# IC3.net
KiCad netlist of a schematic drawn in Altium Designer
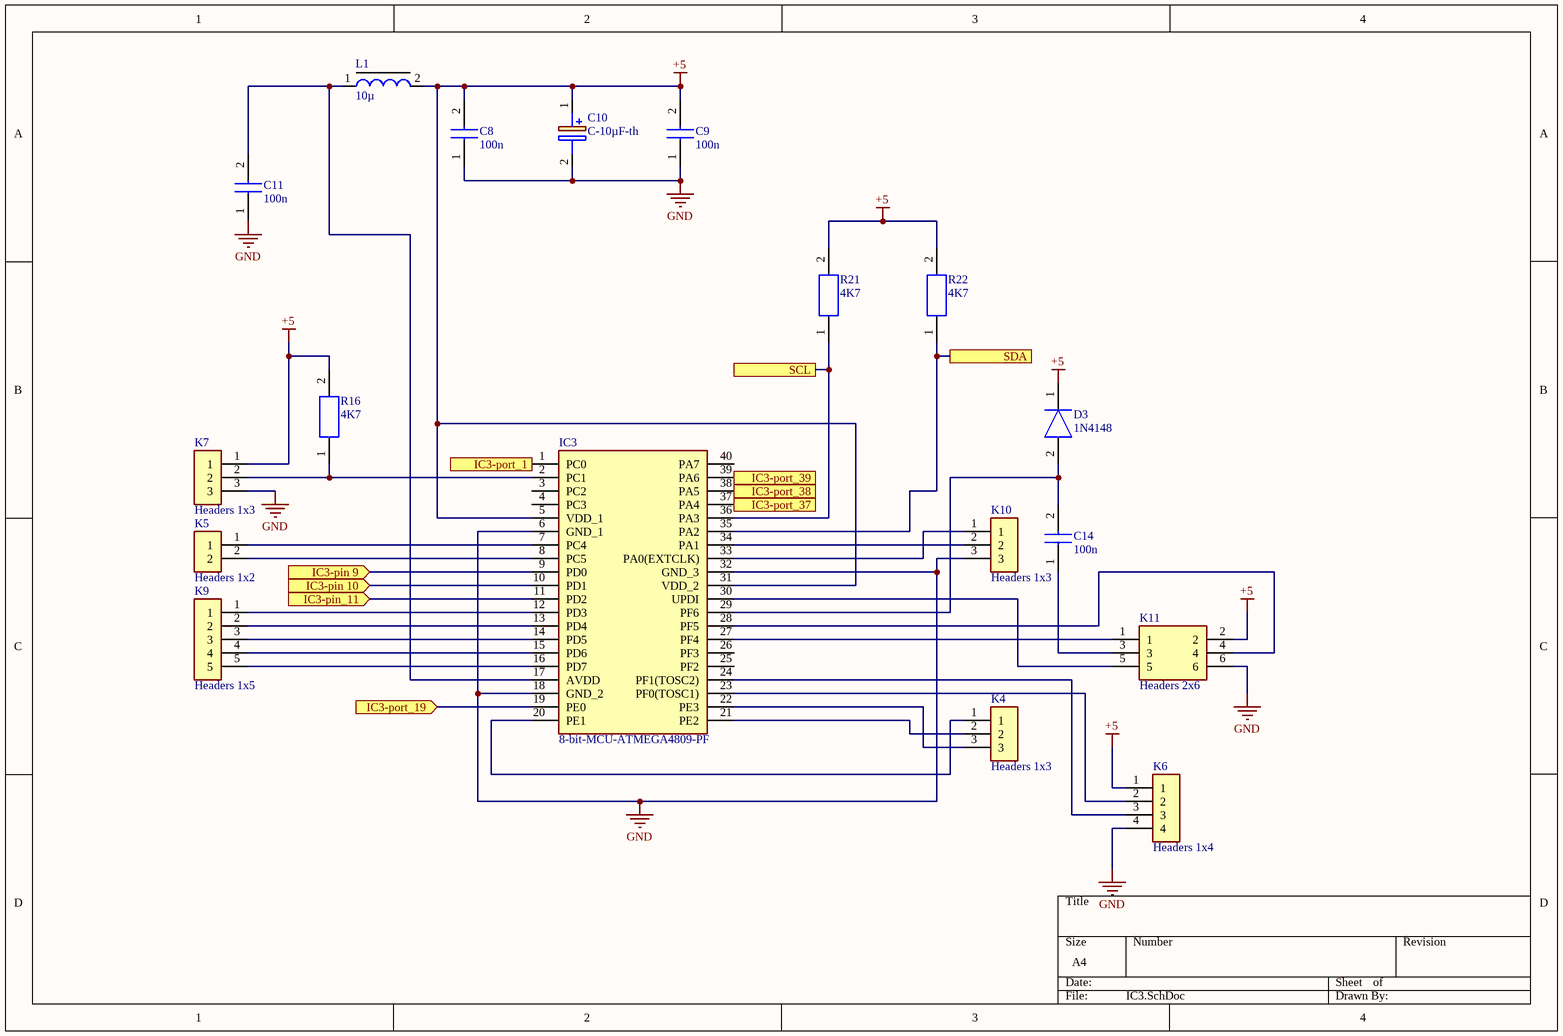
[diagram p0: IC3.SchDoc]

(export (version "E")
  (design (tool "Eeschema 10.0.6"))
  (components
    (comp (ref "C8")
      (value "100n")
      (footprint "C-0805-smd")
      (description "Capacitor")
      (fields (field (name "MANUFACTURER_PART_NUMBER") "C0805C301G5GACTU"))
      (libsource (lib "project-2022") (part "C-0805-smd"))
    )
    (comp (ref "C9")
      (value "100n")
      (footprint "C-0805-smd")
      (description "Capacitor")
      (fields (field (name "MANUFACTURER_PART_NUMBER") "C0805C301G5GACTU"))
      (libsource (lib "project-2022") (part "C-0805-smd"))
    )
    (comp (ref "C10")
      (value "C-10µF-th")
      (footprint "C-10µF-th")
      (description "Capacitor Polarised")
      (fields
        (field (name "MOUSER2 PART NUMBER") "667-ECA-1HM100I")
        (field (name "MANUFACTURER_PART_NUMBER") "ECA-1HM100I")
      )
      (libsource (lib "project-2022") (part "C-10µF-th"))
    )
    (comp (ref "C11")
      (value "100n")
      (footprint "C-0805-smd")
      (description "Capacitor")
      (fields (field (name "MANUFACTURER_PART_NUMBER") "C0805C301G5GACTU"))
      (libsource (lib "project-2022") (part "C-0805-smd"))
    )
    (comp (ref "C14")
      (value "100n")
      (footprint "C-0805-smd")
      (description "Capacitor")
      (fields (field (name "MANUFACTURER_PART_NUMBER") "C0805C301G5GACTU"))
      (libsource (lib "project-2022") (part "C-0805-smd"))
    )
    (comp (ref "D3")
      (value "1N4148")
      (footprint "1N4148")
      (description "Diode")
      (libsource (lib "project-2022") (part "1N4148"))
    )
    (comp (ref "IC3")
      (value "8-bit-MCU-ATMEGA4809-PF")
      (footprint "8-bit-MCU-ATMEGA4809-PF")
      (description "Integrated Circuit")
      (fields
        (field (name "MOUSER2 PART NUMBER") "556-ATMEGA4809-PF")
        (field (name "MANUFACTURER_PART_NUMBER") "ATMEGA4809-PF")
      )
      (libsource (lib "project-2022") (part "8-bit-MCU-ATMEGA4809-PF"))
    )
    (comp (ref "K4")
      (value "Headers 1x3")
      (footprint "Headers 1x3")
      (description "Connector")
      (fields (field (name "MANUFACTURER_PART_NUMBER") "2-826646-0"))
      (libsource (lib "") (part "Headers 1x3_1"))
    )
    (comp (ref "K5")
      (value "Headers 1x2")
      (footprint "Headers 1x2")
      (description "Connector")
      (fields (field (name "MANUFACTURER_PART_NUMBER") "2-826646-0"))
      (libsource (lib "project-2022") (part "Headers 1x2"))
    )
    (comp (ref "K6")
      (value "Headers 1x4")
      (footprint "Headers 1x4")
      (description "Connector")
      (fields (field (name "MANUFACTURER_PART_NUMBER") "2-826646-0"))
      (libsource (lib "project-2022") (part "Headers 1x4"))
    )
    (comp (ref "K7")
      (value "Headers 1x3")
      (footprint "Headers 1x3")
      (description "Connector")
      (fields (field (name "MANUFACTURER_PART_NUMBER") "2-826646-0"))
      (libsource (lib "project-2022") (part "Headers 1x3"))
    )
    (comp (ref "K9")
      (value "Headers 1x5")
      (footprint "Headers 1x5")
      (description "Connector")
      (fields (field (name "MANUFACTURER_PART_NUMBER") "2-826646-0"))
      (libsource (lib "project-2022") (part "Headers 1x5"))
    )
    (comp (ref "K10")
      (value "Headers 1x3")
      (footprint "Headers 1x3")
      (description "Connector")
      (fields (field (name "MANUFACTURER_PART_NUMBER") "2-826646-0"))
      (libsource (lib "") (part "Headers 1x3_1"))
    )
    (comp (ref "K11")
      (value "Headers 2x6")
      (footprint "Headers 2x6")
      (description "Connector")
      (fields
        (field (name "MOUSER2 PART NUMBER") "855-M20-9761042")
        (field (name "MANUFACTURER_PART_NUMBER") "M20-9761042")
      )
      (libsource (lib "project-2022") (part "Headers 2x6"))
    )
    (comp (ref "L1")
      (value "10µ")
      (footprint "Smorespoel-10µH-130mA")
      (description "THT Common Mode Power Line Choke WE-CMB, L = 1.00 mH")
      (libsource (lib "project-2022") (part "Smorespoel-10µH-130mA"))
    )
    (comp (ref "R16")
      (value "4K7")
      (footprint "R-0805")
      (description "Resistor")
      (fields (field (name "MANUFACTURER_PART_NUMBER") "TNPU0805500RAZEN00"))
      (libsource (lib "project-2022") (part "R-0805"))
    )
    (comp (ref "R21")
      (value "4K7")
      (footprint "R-0805")
      (description "Resistor")
      (fields (field (name "MANUFACTURER_PART_NUMBER") "TNPU0805500RAZEN00"))
      (libsource (lib "project-2022") (part "R-0805"))
    )
    (comp (ref "R22")
      (value "4K7")
      (footprint "R-0805")
      (description "Resistor")
      (fields (field (name "MANUFACTURER_PART_NUMBER") "TNPU0805500RAZEN00"))
      (libsource (lib "project-2022") (part "R-0805"))
    )
  )
  (nets
    (net (code "1") (name "+5") (class "Default")
      (node (ref "C10") (pin "1") (pinfunction "+_1") (pintype "passive"))
      (node (ref "C8") (pin "2") (pinfunction "2_2") (pintype "passive"))
      (node (ref "C9") (pin "2") (pinfunction "2_2") (pintype "passive"))
      (node (ref "D3") (pin "1") (pinfunction "K_1") (pintype "passive"))
      (node (ref "IC3") (pin "31") (pinfunction "VDD_2_31") (pintype "passive"))
      (node (ref "IC3") (pin "5") (pinfunction "VDD_1_5") (pintype "passive"))
      (node (ref "K11") (pin "2") (pinfunction "2_2") (pintype "passive"))
      (node (ref "K6") (pin "1") (pinfunction "1_1") (pintype "passive"))
      (node (ref "K7") (pin "1") (pinfunction "1_1") (pintype "passive"))
      (node (ref "L1") (pin "2") (pinfunction "7_2") (pintype "passive"))
      (node (ref "R16") (pin "2") (pinfunction "2_2") (pintype "passive"))
      (node (ref "R21") (pin "2") (pinfunction "2_2") (pintype "passive"))
      (node (ref "R22") (pin "2") (pinfunction "2_2") (pintype "passive"))
    )
    (net (code "2") (name "/IC3-pin 9") (class "Default")
      (node (ref "IC3") (pin "9") (pinfunction "PD0_9") (pintype "passive"))
    )
    (net (code "3") (name "/IC3-pin 10") (class "Default")
      (node (ref "IC3") (pin "10") (pinfunction "PD1_10") (pintype "passive"))
    )
    (net (code "4") (name "/IC3-pin_11") (class "Default")
      (node (ref "IC3") (pin "11") (pinfunction "PD2_11") (pintype "passive"))
    )
    (net (code "5") (name "/IC3-port_1") (class "Default")
      (node (ref "IC3") (pin "1") (pinfunction "PC0_1") (pintype "passive"))
    )
    (net (code "6") (name "/IC3-port_19") (class "Default")
      (node (ref "IC3") (pin "19") (pinfunction "PE0_19") (pintype "passive"))
    )
    (net (code "7") (name "/IC3-port_37") (class "Default")
      (node (ref "IC3") (pin "37") (pinfunction "PA4_37") (pintype "passive"))
    )
    (net (code "8") (name "/IC3-port_38") (class "Default")
      (node (ref "IC3") (pin "38") (pinfunction "PA5_38") (pintype "passive"))
    )
    (net (code "9") (name "/IC3-port_39") (class "Default")
      (node (ref "IC3") (pin "39") (pinfunction "PA6_39") (pintype "passive"))
    )
    (net (code "10") (name "/SCL") (class "Default")
      (node (ref "IC3") (pin "36") (pinfunction "PA3_36") (pintype "passive"))
      (node (ref "R21") (pin "1") (pinfunction "1_1") (pintype "passive"))
    )
    (net (code "11") (name "/SDA") (class "Default")
      (node (ref "IC3") (pin "35") (pinfunction "PA2_35") (pintype "passive"))
      (node (ref "R22") (pin "1") (pinfunction "1_1") (pintype "passive"))
    )
    (net (code "12") (name "GND") (class "Default")
      (node (ref "C10") (pin "2") (pinfunction "-_2") (pintype "passive"))
      (node (ref "C11") (pin "1") (pinfunction "1_1") (pintype "passive"))
      (node (ref "C8") (pin "1") (pinfunction "1_1") (pintype "passive"))
      (node (ref "C9") (pin "1") (pinfunction "1_1") (pintype "passive"))
      (node (ref "IC3") (pin "18") (pinfunction "GND_2_18") (pintype "passive"))
      (node (ref "IC3") (pin "32") (pinfunction "GND_3_32") (pintype "passive"))
      (node (ref "IC3") (pin "6") (pinfunction "GND_1_6") (pintype "passive"))
      (node (ref "K10") (pin "3") (pinfunction "3_3") (pintype "passive"))
      (node (ref "K11") (pin "6") (pinfunction "6_6") (pintype "passive"))
      (node (ref "K6") (pin "4") (pinfunction "4_4") (pintype "passive"))
      (node (ref "K7") (pin "3") (pinfunction "3_3") (pintype "passive"))
    )
    (net (code "13") (name "Net-(C14-Pad1)") (class "Default")
      (node (ref "C14") (pin "1") (pinfunction "1_1") (pintype "passive"))
      (node (ref "K11") (pin "3") (pinfunction "3_3") (pintype "passive"))
    )
    (net (code "14") (name "Net-(D3-A)") (class "Default")
      (node (ref "C14") (pin "2") (pinfunction "2_2") (pintype "passive"))
      (node (ref "D3") (pin "2") (pinfunction "A_2") (pintype "passive"))
      (node (ref "IC3") (pin "29") (pinfunction "PF6_29") (pintype "passive"))
    )
    (net (code "15") (name "Net-(IC3-AVDD)") (class "Default")
      (node (ref "C11") (pin "2") (pinfunction "2_2") (pintype "passive"))
      (node (ref "IC3") (pin "17") (pinfunction "AVDD_17") (pintype "passive"))
      (node (ref "L1") (pin "1") (pinfunction "4_1") (pintype "passive"))
    )
    (net (code "16") (name "Net-(IC3-PA0(EXTCLK))") (class "Default")
      (node (ref "IC3") (pin "33") (pinfunction "PA0(EXTCLK)_33") (pintype "passive"))
      (node (ref "K10") (pin "1") (pinfunction "1_1") (pintype "passive"))
    )
    (net (code "17") (name "Net-(IC3-PA1)") (class "Default")
      (node (ref "IC3") (pin "34") (pinfunction "PA1_34") (pintype "passive"))
      (node (ref "K10") (pin "2") (pinfunction "2_2") (pintype "passive"))
    )
    (net (code "18") (name "Net-(IC3-PC1)") (class "Default")
      (node (ref "IC3") (pin "2") (pinfunction "PC1_2") (pintype "passive"))
      (node (ref "K7") (pin "2") (pinfunction "2_2") (pintype "passive"))
      (node (ref "R16") (pin "1") (pinfunction "1_1") (pintype "passive"))
    )
    (net (code "19") (name "Net-(IC3-PC4)") (class "Default")
      (node (ref "IC3") (pin "7") (pinfunction "PC4_7") (pintype "passive"))
      (node (ref "K5") (pin "1") (pinfunction "1_1") (pintype "passive"))
    )
    (net (code "20") (name "Net-(IC3-PC5)") (class "Default")
      (node (ref "IC3") (pin "8") (pinfunction "PC5_8") (pintype "passive"))
      (node (ref "K5") (pin "2") (pinfunction "2_2") (pintype "passive"))
    )
    (net (code "21") (name "Net-(IC3-PD3)") (class "Default")
      (node (ref "IC3") (pin "12") (pinfunction "PD3_12") (pintype "passive"))
      (node (ref "K9") (pin "1") (pinfunction "1_1") (pintype "passive"))
    )
    (net (code "22") (name "Net-(IC3-PD4)") (class "Default")
      (node (ref "IC3") (pin "13") (pinfunction "PD4_13") (pintype "passive"))
      (node (ref "K9") (pin "2") (pinfunction "2_2") (pintype "passive"))
    )
    (net (code "23") (name "Net-(IC3-PD5)") (class "Default")
      (node (ref "IC3") (pin "14") (pinfunction "PD5_14") (pintype "passive"))
      (node (ref "K9") (pin "3") (pinfunction "3_3") (pintype "passive"))
    )
    (net (code "24") (name "Net-(IC3-PD6)") (class "Default")
      (node (ref "IC3") (pin "15") (pinfunction "PD6_15") (pintype "passive"))
      (node (ref "K9") (pin "4") (pinfunction "4_4") (pintype "passive"))
    )
    (net (code "25") (name "Net-(IC3-PD7)") (class "Default")
      (node (ref "IC3") (pin "16") (pinfunction "PD7_16") (pintype "passive"))
      (node (ref "K9") (pin "5") (pinfunction "5_5") (pintype "passive"))
    )
    (net (code "26") (name "Net-(IC3-PE1)") (class "Default")
      (node (ref "IC3") (pin "20") (pinfunction "PE1_20") (pintype "passive"))
      (node (ref "K4") (pin "1") (pinfunction "1_1") (pintype "passive"))
    )
    (net (code "27") (name "Net-(IC3-PE2)") (class "Default")
      (node (ref "IC3") (pin "21") (pinfunction "PE2_21") (pintype "passive"))
      (node (ref "K4") (pin "2") (pinfunction "2_2") (pintype "passive"))
    )
    (net (code "28") (name "Net-(IC3-PE3)") (class "Default")
      (node (ref "IC3") (pin "22") (pinfunction "PE3_22") (pintype "passive"))
      (node (ref "K4") (pin "3") (pinfunction "3_3") (pintype "passive"))
    )
    (net (code "29") (name "Net-(IC3-PF0(TOSC1))") (class "Default")
      (node (ref "IC3") (pin "23") (pinfunction "PF0(TOSC1)_23") (pintype "passive"))
      (node (ref "K6") (pin "2") (pinfunction "2_2") (pintype "passive"))
    )
    (net (code "30") (name "Net-(IC3-PF1(TOSC2))") (class "Default")
      (node (ref "IC3") (pin "24") (pinfunction "PF1(TOSC2)_24") (pintype "passive"))
      (node (ref "K6") (pin "3") (pinfunction "3_3") (pintype "passive"))
    )
    (net (code "31") (name "Net-(IC3-PF4)") (class "Default")
      (node (ref "IC3") (pin "27") (pinfunction "PF4_27") (pintype "passive"))
      (node (ref "K11") (pin "1") (pinfunction "1_1") (pintype "passive"))
    )
    (net (code "32") (name "Net-(IC3-PF5)") (class "Default")
      (node (ref "IC3") (pin "28") (pinfunction "PF5_28") (pintype "passive"))
      (node (ref "K11") (pin "4") (pinfunction "4_4") (pintype "passive"))
    )
    (net (code "33") (name "Net-(IC3-UPDI)") (class "Default")
      (node (ref "IC3") (pin "30") (pinfunction "UPDI_30") (pintype "passive"))
      (node (ref "K11") (pin "5") (pinfunction "5_5") (pintype "passive"))
    )
    (net (code "34") (name "unconnected-(IC3-PA7-Pad40)") (class "Default")
      (node (ref "IC3") (pin "40") (pinfunction "PA7_40") (pintype "passive"))
    )
    (net (code "35") (name "unconnected-(IC3-PC2-Pad3)") (class "Default")
      (node (ref "IC3") (pin "3") (pinfunction "PC2_3") (pintype "passive"))
    )
    (net (code "36") (name "unconnected-(IC3-PC3-Pad4)") (class "Default")
      (node (ref "IC3") (pin "4") (pinfunction "PC3_4") (pintype "passive"))
    )
    (net (code "37") (name "unconnected-(IC3-PF2-Pad25)") (class "Default")
      (node (ref "IC3") (pin "25") (pinfunction "PF2_25") (pintype "passive"))
    )
    (net (code "38") (name "unconnected-(IC3-PF3-Pad26)") (class "Default")
      (node (ref "IC3") (pin "26") (pinfunction "PF3_26") (pintype "passive"))
    )
  )
)
